# Memoria.net
KiCad netlist of a schematic drawn in Altium Designer
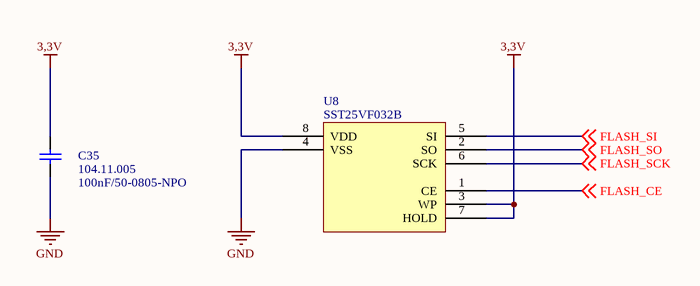
[diagram p0: Memoria.SchDoc]

(export (version "E")
  (design (tool "Eeschema 10.0.6"))
  (components
    (comp (ref "C35")
      (value "100nF/50-0805-NPO")
      (footprint "0805-REVISADO ONDA")
      (fields (field (name "ERP") "104.11.005"))
      (libsource (lib "AquinoLib") (part "100nF/50-0805-NPO"))
    )
    (comp (ref "U8")
      (value "SST25VF032B")
      (footprint "SOIC-08")
      (libsource (lib "ChaveDigital3") (part "SST25VF032B"))
    )
  )
  (nets
    (net (code "1") (name "3,3V") (class "Default")
      (node (ref "C35") (pin "2") (pinfunction "2_2") (pintype "passive"))
      (node (ref "U8") (pin "3") (pinfunction "WP_3") (pintype "passive"))
      (node (ref "U8") (pin "7") (pinfunction "HOLD_7") (pintype "passive"))
      (node (ref "U8") (pin "8") (pinfunction "VDD_8") (pintype "passive"))
    )
    (net (code "2") (name "FLASH_CE") (class "Default")
      (node (ref "U8") (pin "1") (pinfunction "CE_1") (pintype "passive"))
    )
    (net (code "3") (name "FLASH_SCK") (class "Default")
      (node (ref "U8") (pin "6") (pinfunction "SCK_6") (pintype "passive"))
    )
    (net (code "4") (name "FLASH_SI") (class "Default")
      (node (ref "U8") (pin "5") (pinfunction "SI_5") (pintype "passive"))
    )
    (net (code "5") (name "FLASH_SO") (class "Default")
      (node (ref "U8") (pin "2") (pinfunction "SO_2") (pintype "passive"))
    )
    (net (code "6") (name "GND") (class "Default")
      (node (ref "C35") (pin "1") (pinfunction "1_1") (pintype "passive"))
      (node (ref "U8") (pin "4") (pinfunction "VSS_4") (pintype "passive"))
    )
  )
)
